# SENSORS.net
KiCad netlist of a schematic drawn in Altium Designer
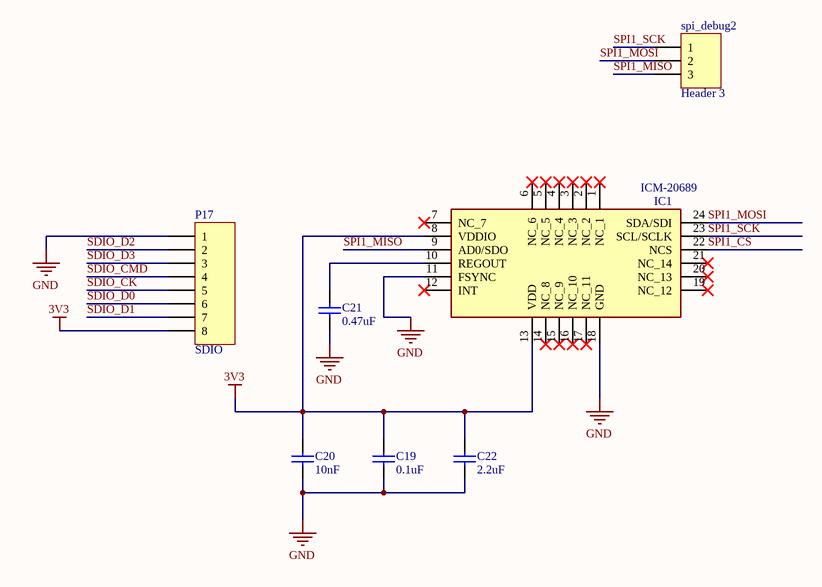
[diagram p0: SENSORS.SchDoc]

(export (version "E")
  (design (tool "Eeschema 10.0.6"))
  (components
    (comp (ref "C19")
      (value "0.1uF")
      (footprint "stm_copter:CAPC2012X145N")
      (description "Capacitor (Semiconductor SIM Model)")
      (fields (field (name "PUBLISHER") "Altium Limited"))
      (libsource (lib "syhaunguyen") (part "Cap Semi"))
    )
    (comp (ref "C20")
      (value "10nF")
      (footprint "stm_copter:CAPC2012X145N")
      (description "Capacitor (Semiconductor SIM Model)")
      (fields (field (name "PUBLISHER") "Altium Limited"))
      (libsource (lib "syhaunguyen") (part "Cap Semi"))
    )
    (comp (ref "C21")
      (value "0.47uF")
      (footprint "stm_copter:CAPC1608X90N")
      (description "Capacitor (Semiconductor SIM Model)")
      (fields (field (name "PUBLISHER") "Altium Limited"))
      (libsource (lib "syhaunguyen") (part "Cap Semi"))
    )
    (comp (ref "C22")
      (value "2.2uF")
      (footprint "stm_copter:CAPC3216X125N")
      (description "Capacitor (Semiconductor SIM Model)")
      (fields (field (name "PUBLISHER") "Altium Limited"))
      (libsource (lib "syhaunguyen") (part "Cap Semi"))
    )
    (comp (ref "IC1")
      (value "ICM-20689")
      (footprint "SamacSys:ICM20689")
      (description "Integrated Circuit")
      (fields (field (name "MOUSER PART NUMBER") "410-ICM-20689"))
      (libsource (lib "*") (part "ICM-20689"))
    )
    (comp (ref "P17")
      (value "SDIO")
      (footprint "HDR1X8")
      (description "Header, 8-Pin")
      (fields (field (name "PUBLISHER") "Altium Limited"))
      (libsource (lib "Miscellaneous Connectors") (part "Header 8"))
    )
    (comp (ref "spi_debug2")
      (value "Header 3")
      (footprint "HDR1X3")
      (description "Header, 3-Pin")
      (fields (field (name "PUBLISHER") "Altium Limited"))
      (libsource (lib "Miscellaneous Connectors") (part "Header 3"))
    )
  )
  (nets
    (net (code "1") (name "/SDIO_CK") (class "Default")
      (node (ref "P17") (pin "5") (pinfunction "5_5") (pintype "passive"))
    )
    (net (code "2") (name "/SDIO_CMD") (class "Default")
      (node (ref "P17") (pin "4") (pinfunction "4_4") (pintype "passive"))
    )
    (net (code "3") (name "/SDIO_D0") (class "Default")
      (node (ref "P17") (pin "6") (pinfunction "6_6") (pintype "passive"))
    )
    (net (code "4") (name "/SDIO_D1") (class "Default")
      (node (ref "P17") (pin "7") (pinfunction "7_7") (pintype "passive"))
    )
    (net (code "5") (name "/SDIO_D2") (class "Default")
      (node (ref "P17") (pin "2") (pinfunction "2_2") (pintype "passive"))
    )
    (net (code "6") (name "/SDIO_D3") (class "Default")
      (node (ref "P17") (pin "3") (pinfunction "3_3") (pintype "passive"))
    )
    (net (code "7") (name "/SPI1_CS") (class "Default")
      (node (ref "IC1") (pin "22") (pinfunction "NCS_22") (pintype "passive"))
    )
    (net (code "8") (name "/SPI1_MISO") (class "Default")
      (node (ref "IC1") (pin "9") (pinfunction "AD0/SDO_9") (pintype "passive"))
      (node (ref "spi_debug2") (pin "3") (pinfunction "3_3") (pintype "passive"))
    )
    (net (code "9") (name "/SPI1_MOSI") (class "Default")
      (node (ref "IC1") (pin "24") (pinfunction "SDA/SDI_24") (pintype "passive"))
      (node (ref "spi_debug2") (pin "2") (pinfunction "2_2") (pintype "passive"))
    )
    (net (code "10") (name "/SPI1_SCK") (class "Default")
      (node (ref "IC1") (pin "23") (pinfunction "SCL/SCLK_23") (pintype "passive"))
      (node (ref "spi_debug2") (pin "1") (pinfunction "1_1") (pintype "passive"))
    )
    (net (code "11") (name "3V3") (class "Default")
      (node (ref "C19") (pin "1") (pinfunction "1_1") (pintype "passive"))
      (node (ref "C20") (pin "1") (pinfunction "1_1") (pintype "passive"))
      (node (ref "C22") (pin "2") (pinfunction "2_2") (pintype "passive"))
      (node (ref "IC1") (pin "13") (pinfunction "VDD_13") (pintype "passive"))
      (node (ref "IC1") (pin "8") (pinfunction "VDDIO_8") (pintype "passive"))
      (node (ref "P17") (pin "8") (pinfunction "8_8") (pintype "passive"))
    )
    (net (code "12") (name "GND") (class "Default")
      (node (ref "C19") (pin "2") (pinfunction "2_2") (pintype "passive"))
      (node (ref "C20") (pin "2") (pinfunction "2_2") (pintype "passive"))
      (node (ref "C21") (pin "1") (pinfunction "1_1") (pintype "passive"))
      (node (ref "C22") (pin "1") (pinfunction "1_1") (pintype "passive"))
      (node (ref "IC1") (pin "11") (pinfunction "FSYNC_11") (pintype "passive"))
      (node (ref "IC1") (pin "18") (pinfunction "GND_18") (pintype "passive"))
      (node (ref "P17") (pin "1") (pinfunction "1_1") (pintype "passive"))
    )
    (net (code "13") (name "Net-(IC1-REGOUT)") (class "Default")
      (node (ref "C21") (pin "2") (pinfunction "2_2") (pintype "passive"))
      (node (ref "IC1") (pin "10") (pinfunction "REGOUT_10") (pintype "passive"))
    )
    (net (code "14") (name "unconnected-(IC1-INT-Pad12)") (class "Default")
      (node (ref "IC1") (pin "12") (pinfunction "INT_12") (pintype "passive+no_connect"))
    )
    (net (code "15") (name "unconnected-(IC1-NC_1-Pad1)") (class "Default")
      (node (ref "IC1") (pin "1") (pinfunction "NC_1_1") (pintype "passive+no_connect"))
    )
    (net (code "16") (name "unconnected-(IC1-NC_2-Pad2)") (class "Default")
      (node (ref "IC1") (pin "2") (pinfunction "NC_2_2") (pintype "passive+no_connect"))
    )
    (net (code "17") (name "unconnected-(IC1-NC_3-Pad3)") (class "Default")
      (node (ref "IC1") (pin "3") (pinfunction "NC_3_3") (pintype "passive+no_connect"))
    )
    (net (code "18") (name "unconnected-(IC1-NC_4-Pad4)") (class "Default")
      (node (ref "IC1") (pin "4") (pinfunction "NC_4_4") (pintype "passive+no_connect"))
    )
    (net (code "19") (name "unconnected-(IC1-NC_5-Pad5)") (class "Default")
      (node (ref "IC1") (pin "5") (pinfunction "NC_5_5") (pintype "passive+no_connect"))
    )
    (net (code "20") (name "unconnected-(IC1-NC_6-Pad6)") (class "Default")
      (node (ref "IC1") (pin "6") (pinfunction "NC_6_6") (pintype "passive+no_connect"))
    )
    (net (code "21") (name "unconnected-(IC1-NC_7-Pad7)") (class "Default")
      (node (ref "IC1") (pin "7") (pinfunction "NC_7_7") (pintype "passive+no_connect"))
    )
    (net (code "22") (name "unconnected-(IC1-NC_8-Pad14)") (class "Default")
      (node (ref "IC1") (pin "14") (pinfunction "NC_8_14") (pintype "passive+no_connect"))
    )
    (net (code "23") (name "unconnected-(IC1-NC_9-Pad15)") (class "Default")
      (node (ref "IC1") (pin "15") (pinfunction "NC_9_15") (pintype "passive+no_connect"))
    )
    (net (code "24") (name "unconnected-(IC1-NC_10-Pad16)") (class "Default")
      (node (ref "IC1") (pin "16") (pinfunction "NC_10_16") (pintype "passive+no_connect"))
    )
    (net (code "25") (name "unconnected-(IC1-NC_11-Pad17)") (class "Default")
      (node (ref "IC1") (pin "17") (pinfunction "NC_11_17") (pintype "passive+no_connect"))
    )
    (net (code "26") (name "unconnected-(IC1-NC_12-Pad19)") (class "Default")
      (node (ref "IC1") (pin "19") (pinfunction "NC_12_19") (pintype "passive+no_connect"))
    )
    (net (code "27") (name "unconnected-(IC1-NC_13-Pad20)") (class "Default")
      (node (ref "IC1") (pin "20") (pinfunction "NC_13_20") (pintype "passive+no_connect"))
    )
    (net (code "28") (name "unconnected-(IC1-NC_14-Pad21)") (class "Default")
      (node (ref "IC1") (pin "21") (pinfunction "NC_14_21") (pintype "passive+no_connect"))
    )
  )
)
